# miditendo_rev2.net
KiCad netlist of a schematic drawn in EAGLE
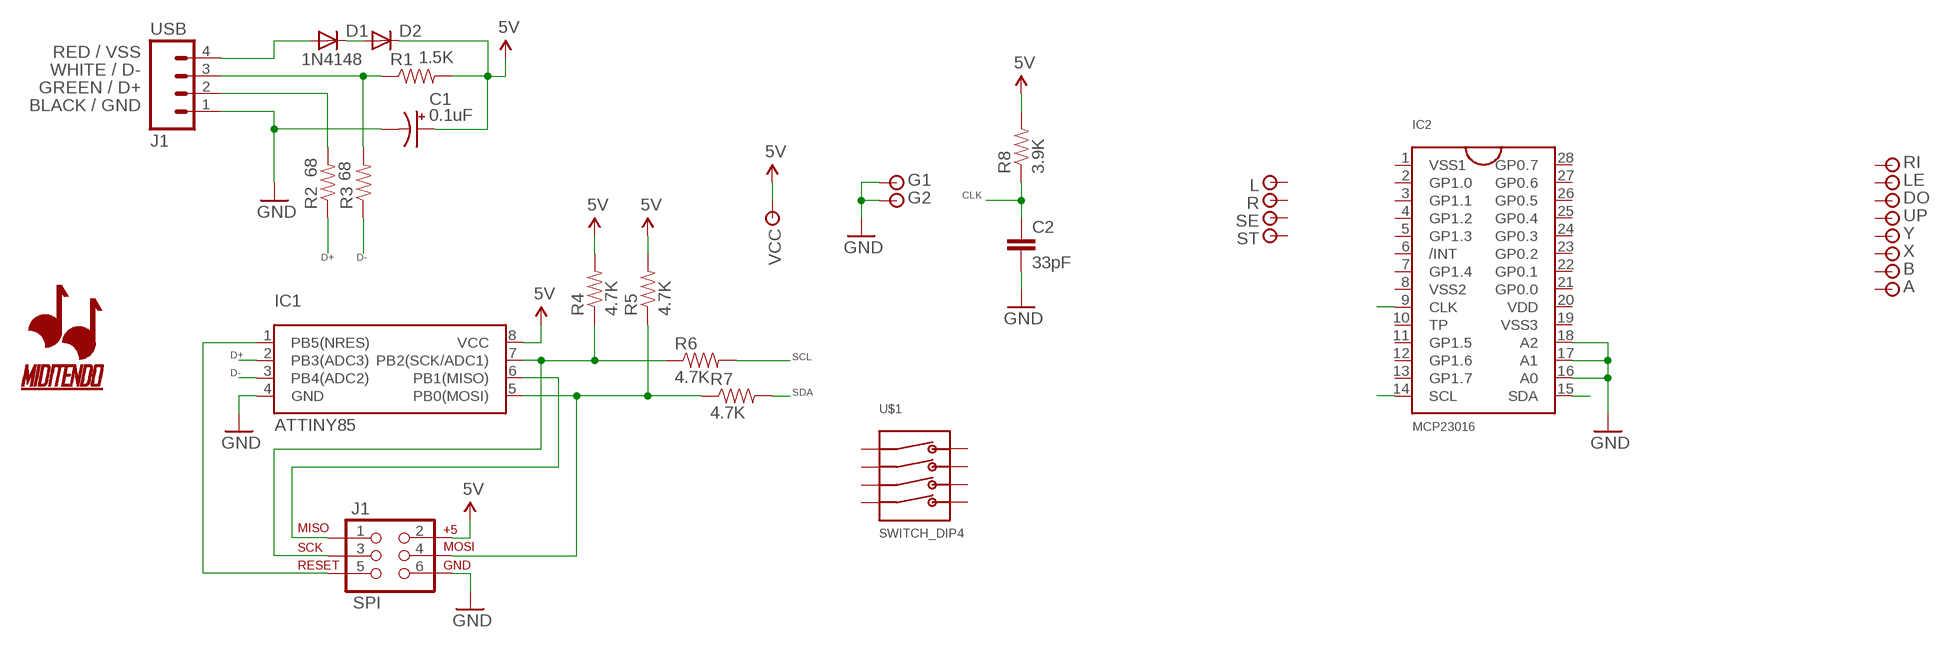
[diagram p0: schematic, sheet 1]

(export (version "E")
  (design (tool "Eeschema 10.0.6"))
  (components
    (comp (ref "A")
      (value "WIRE_JOINT")
      (footprint "eagle-import:THSOLDERPOINT")
      (libsource (lib "eagle-import") (part "WIRE_JOINT"))
    )
    (comp (ref "B")
      (value "WIRE_JOINT")
      (footprint "eagle-import:THSOLDERPOINT")
      (libsource (lib "eagle-import") (part "WIRE_JOINT"))
    )
    (comp (ref "C1")
      (value "0.1uF")
      (footprint "eagle-import:POLCAP_2.54")
      (libsource (lib "eagle-import") (part "POLARIZEDCAPACITORTH_2.54"))
    )
    (comp (ref "C2")
      (value "33pF")
      (footprint "eagle-import:0805")
      (libsource (lib "eagle-import") (part "CAPACITOR0805"))
    )
    (comp (ref "D1")
      (value "LL4148SOD-80C")
      (footprint "eagle-import:SOD-80C")
      (libsource (lib "eagle-import") (part "LL4148SOD-80C"))
    )
    (comp (ref "D2")
      (value "1N4148")
      (footprint "eagle-import:SOD-80C")
      (libsource (lib "eagle-import") (part "LL4148SOD-80C"))
    )
    (comp (ref "DO")
      (value "WIRE_JOINT")
      (footprint "eagle-import:THSOLDERPOINT")
      (libsource (lib "eagle-import") (part "WIRE_JOINT"))
    )
    (comp (ref "G1")
      (value "WIRE_JOINT")
      (footprint "eagle-import:THSOLDERPOINT")
      (libsource (lib "eagle-import") (part "WIRE_JOINT"))
    )
    (comp (ref "G2")
      (value "WIRE_JOINT")
      (footprint "eagle-import:THSOLDERPOINT")
      (libsource (lib "eagle-import") (part "WIRE_JOINT"))
    )
    (comp (ref "IC1")
      (value "ATTINY85")
      (footprint "eagle-import:SOIC8-EIAJ")
      (libsource (lib "eagle-import") (part "ATTINY85SOIC"))
    )
    (comp (ref "IC2")
      (value "MCP23016")
      (footprint "eagle-import:SOIC28")
      (libsource (lib "eagle-import") (part "MCP23016SOIC28"))
    )
    (comp (ref "J1")
      (value "SPI")
      (footprint "eagle-import:2X3-NS")
      (libsource (lib "eagle-import") (part "AVR_SPI_PRG_6NS"))
    )
    (comp (ref "L")
      (value "WIRE_JOINT")
      (footprint "eagle-import:THSOLDERPOINT")
      (libsource (lib "eagle-import") (part "WIRE_JOINT"))
    )
    (comp (ref "LE")
      (value "WIRE_JOINT")
      (footprint "eagle-import:THSOLDERPOINT")
      (libsource (lib "eagle-import") (part "WIRE_JOINT"))
    )
    (comp (ref "R")
      (value "WIRE_JOINT")
      (footprint "eagle-import:THSOLDERPOINT")
      (libsource (lib "eagle-import") (part "WIRE_JOINT"))
    )
    (comp (ref "R1")
      (value "1.5K")
      (footprint "eagle-import:0805")
      (libsource (lib "eagle-import") (part "RESISTOR0805"))
    )
    (comp (ref "R2")
      (value "68")
      (footprint "eagle-import:0805")
      (libsource (lib "eagle-import") (part "RESISTOR0805"))
    )
    (comp (ref "R3")
      (value "68")
      (footprint "eagle-import:0805")
      (libsource (lib "eagle-import") (part "RESISTOR0805"))
    )
    (comp (ref "R4")
      (value "4.7K")
      (footprint "eagle-import:0805")
      (libsource (lib "eagle-import") (part "RESISTOR0805"))
    )
    (comp (ref "R5")
      (value "4.7K")
      (footprint "eagle-import:0805")
      (libsource (lib "eagle-import") (part "RESISTOR0805"))
    )
    (comp (ref "R6")
      (value "4.7K")
      (footprint "eagle-import:0805")
      (libsource (lib "eagle-import") (part "RESISTOR0805"))
    )
    (comp (ref "R7")
      (value "4.7K")
      (footprint "eagle-import:0805")
      (libsource (lib "eagle-import") (part "RESISTOR0805"))
    )
    (comp (ref "R8")
      (value "3.9K")
      (footprint "eagle-import:0805")
      (libsource (lib "eagle-import") (part "RESISTOR0805"))
    )
    (comp (ref "RI")
      (value "WIRE_JOINT")
      (footprint "eagle-import:THSOLDERPOINT")
      (libsource (lib "eagle-import") (part "WIRE_JOINT"))
    )
    (comp (ref "SE")
      (value "WIRE_JOINT")
      (footprint "eagle-import:THSOLDERPOINT")
      (libsource (lib "eagle-import") (part "WIRE_JOINT"))
    )
    (comp (ref "ST")
      (value "WIRE_JOINT")
      (footprint "eagle-import:THSOLDERPOINT")
      (libsource (lib "eagle-import") (part "WIRE_JOINT"))
    )
    (comp (ref "U$1")
      (value "SWITCH_DIP4")
      (footprint "eagle-import:SWITCH_4DIP")
      (libsource (lib "eagle-import") (part "SWITCH_DIP4"))
    )
    (comp (ref "U$2")
      (value "MIDITENDO")
      (footprint "eagle-import:MIDITENDO")
      (libsource (lib "eagle-import") (part "MIDITENDO"))
    )
    (comp (ref "UP")
      (value "WIRE_JOINT")
      (footprint "eagle-import:THSOLDERPOINT")
      (libsource (lib "eagle-import") (part "WIRE_JOINT"))
    )
    (comp (ref "USB")
      (value "J1")
      (footprint "eagle-import:1X04_LONGPADS")
      (libsource (lib "eagle-import") (part "M04LONGPADS"))
    )
    (comp (ref "VCC")
      (value "WIRE_JOINT")
      (footprint "eagle-import:THSOLDERPOINT")
      (libsource (lib "eagle-import") (part "WIRE_JOINT"))
    )
    (comp (ref "X")
      (value "WIRE_JOINT")
      (footprint "eagle-import:THSOLDERPOINT")
      (libsource (lib "eagle-import") (part "WIRE_JOINT"))
    )
    (comp (ref "Y")
      (value "WIRE_JOINT")
      (footprint "eagle-import:THSOLDERPOINT")
      (libsource (lib "eagle-import") (part "WIRE_JOINT"))
    )
  )
  (nets
    (net (code "1") (name "/CLK") (class "Default")
      (node (ref "C2") (pin "1") (pinfunction "1_1") (pintype "passive"))
      (node (ref "IC2") (pin "9") (pinfunction "CLK_9") (pintype "input"))
      (node (ref "R8") (pin "1") (pinfunction "1_1") (pintype "passive"))
    )
    (net (code "2") (name "/D+") (class "Default")
      (node (ref "IC1") (pin "2") (pinfunction "PB3(ADC3)_2") (pintype "bidirectional"))
      (node (ref "R2") (pin "1") (pinfunction "1_1") (pintype "passive"))
    )
    (net (code "3") (name "/D-") (class "Default")
      (node (ref "IC1") (pin "3") (pinfunction "PB4(ADC2)_3") (pintype "bidirectional"))
      (node (ref "R3") (pin "1") (pinfunction "1_1") (pintype "passive"))
    )
    (net (code "4") (name "/SCL") (class "Default")
      (node (ref "IC2") (pin "14") (pinfunction "SCL_14") (pintype "input"))
      (node (ref "R6") (pin "2") (pinfunction "2_2") (pintype "passive"))
    )
    (net (code "5") (name "/SDA") (class "Default")
      (node (ref "IC2") (pin "15") (pinfunction "SDA_15") (pintype "bidirectional"))
      (node (ref "R7") (pin "2") (pinfunction "2_2") (pintype "passive"))
    )
    (net (code "6") (name "/VDD") (class "Default")
      (node (ref "IC2") (pin "20") (pinfunction "VDD_20") (pintype "power_in"))
    )
    (net (code "7") (name "/VSS1") (class "Default")
      (node (ref "IC2") (pin "1") (pinfunction "VSS1_1") (pintype "power_in"))
    )
    (net (code "8") (name "/VSS2") (class "Default")
      (node (ref "IC2") (pin "8") (pinfunction "VSS2_8") (pintype "power_in"))
    )
    (net (code "9") (name "/VSS3") (class "Default")
      (node (ref "IC2") (pin "19") (pinfunction "VSS3_19") (pintype "power_in"))
    )
    (net (code "10") (name "5V") (class "Default")
      (node (ref "C1") (pin "P") (pinfunction "+_P") (pintype "passive"))
      (node (ref "D2") (pin "PC") (pinfunction "C_PC") (pintype "passive"))
      (node (ref "IC1") (pin "8") (pinfunction "VCC_8") (pintype "bidirectional"))
      (node (ref "J1") (pin "2") (pinfunction "2_2") (pintype "passive"))
      (node (ref "R1") (pin "2") (pinfunction "2_2") (pintype "passive"))
      (node (ref "R4") (pin "2") (pinfunction "2_2") (pintype "passive"))
      (node (ref "R5") (pin "2") (pinfunction "2_2") (pintype "passive"))
      (node (ref "R8") (pin "2") (pinfunction "2_2") (pintype "passive"))
      (node (ref "VCC") (pin "P$1") (pinfunction "P$1_P$1") (pintype "passive"))
    )
    (net (code "11") (name "GND") (class "Default")
      (node (ref "C1") (pin "N") (pinfunction "-_N") (pintype "passive"))
      (node (ref "C2") (pin "2") (pinfunction "2_2") (pintype "passive"))
      (node (ref "G1") (pin "P$1") (pinfunction "P$1_P$1") (pintype "passive"))
      (node (ref "G2") (pin "P$1") (pinfunction "P$1_P$1") (pintype "passive"))
      (node (ref "IC1") (pin "4") (pinfunction "GND_4") (pintype "bidirectional"))
      (node (ref "IC2") (pin "16") (pinfunction "A0_16") (pintype "input"))
      (node (ref "IC2") (pin "17") (pinfunction "A1_17") (pintype "input"))
      (node (ref "IC2") (pin "18") (pinfunction "A2_18") (pintype "input"))
      (node (ref "J1") (pin "6") (pinfunction "6_6") (pintype "passive"))
      (node (ref "USB") (pin "1") (pinfunction "1_1") (pintype "passive"))
    )
    (net (code "12") (name "Net-(D1-A)") (class "Default")
      (node (ref "D1") (pin "PA") (pinfunction "A_PA") (pintype "passive"))
      (node (ref "USB") (pin "4") (pinfunction "4_4") (pintype "passive"))
    )
    (net (code "13") (name "Net-(D1-C)") (class "Default")
      (node (ref "D1") (pin "PC") (pinfunction "C_PC") (pintype "passive"))
      (node (ref "D2") (pin "PA") (pinfunction "A_PA") (pintype "passive"))
    )
    (net (code "14") (name "Net-(IC1-PB0(MOSI))") (class "Default")
      (node (ref "IC1") (pin "5") (pinfunction "PB0(MOSI)_5") (pintype "bidirectional"))
      (node (ref "J1") (pin "4") (pinfunction "4_4") (pintype "passive"))
      (node (ref "R5") (pin "1") (pinfunction "1_1") (pintype "passive"))
      (node (ref "R7") (pin "1") (pinfunction "1_1") (pintype "passive"))
    )
    (net (code "15") (name "Net-(IC1-PB1(MISO))") (class "Default")
      (node (ref "IC1") (pin "6") (pinfunction "PB1(MISO)_6") (pintype "bidirectional"))
      (node (ref "J1") (pin "1") (pinfunction "1_1") (pintype "passive"))
    )
    (net (code "16") (name "Net-(IC1-PB2(SCK{slash}ADC1))") (class "Default")
      (node (ref "IC1") (pin "7") (pinfunction "PB2(SCK/ADC1)_7") (pintype "bidirectional"))
      (node (ref "J1") (pin "3") (pinfunction "3_3") (pintype "passive"))
      (node (ref "R4") (pin "1") (pinfunction "1_1") (pintype "passive"))
      (node (ref "R6") (pin "1") (pinfunction "1_1") (pintype "passive"))
    )
    (net (code "17") (name "Net-(IC1-PB5(NRES))") (class "Default")
      (node (ref "IC1") (pin "1") (pinfunction "PB5(NRES)_1") (pintype "bidirectional"))
      (node (ref "J1") (pin "5") (pinfunction "5_5") (pintype "passive"))
    )
    (net (code "18") (name "Net-(R1-Pad1)") (class "Default")
      (node (ref "R1") (pin "1") (pinfunction "1_1") (pintype "passive"))
      (node (ref "R3") (pin "2") (pinfunction "2_2") (pintype "passive"))
      (node (ref "USB") (pin "3") (pinfunction "3_3") (pintype "passive"))
    )
    (net (code "19") (name "Net-(R2-Pad2)") (class "Default")
      (node (ref "R2") (pin "2") (pinfunction "2_2") (pintype "passive"))
      (node (ref "USB") (pin "2") (pinfunction "2_2") (pintype "passive"))
    )
    (net (code "20") (name "unconnected-(A-PadP$1)") (class "Default")
      (node (ref "A") (pin "P$1") (pinfunction "P$1_P$1") (pintype "passive"))
    )
    (net (code "21") (name "unconnected-(B-PadP$1)") (class "Default")
      (node (ref "B") (pin "P$1") (pinfunction "P$1_P$1") (pintype "passive"))
    )
    (net (code "22") (name "unconnected-(DO-PadP$1)") (class "Default")
      (node (ref "DO") (pin "P$1") (pinfunction "P$1_P$1") (pintype "passive"))
    )
    (net (code "23") (name "unconnected-(IC2-GP0.0-Pad21)") (class "Default")
      (node (ref "IC2") (pin "21") (pinfunction "GP0.0_21") (pintype "bidirectional"))
    )
    (net (code "24") (name "unconnected-(IC2-GP0.1-Pad22)") (class "Default")
      (node (ref "IC2") (pin "22") (pinfunction "GP0.1_22") (pintype "bidirectional"))
    )
    (net (code "25") (name "unconnected-(IC2-GP0.2-Pad23)") (class "Default")
      (node (ref "IC2") (pin "23") (pinfunction "GP0.2_23") (pintype "bidirectional"))
    )
    (net (code "26") (name "unconnected-(IC2-GP0.3-Pad24)") (class "Default")
      (node (ref "IC2") (pin "24") (pinfunction "GP0.3_24") (pintype "bidirectional"))
    )
    (net (code "27") (name "unconnected-(IC2-GP0.4-Pad25)") (class "Default")
      (node (ref "IC2") (pin "25") (pinfunction "GP0.4_25") (pintype "bidirectional"))
    )
    (net (code "28") (name "unconnected-(IC2-GP0.5-Pad26)") (class "Default")
      (node (ref "IC2") (pin "26") (pinfunction "GP0.5_26") (pintype "bidirectional"))
    )
    (net (code "29") (name "unconnected-(IC2-GP0.6-Pad27)") (class "Default")
      (node (ref "IC2") (pin "27") (pinfunction "GP0.6_27") (pintype "bidirectional"))
    )
    (net (code "30") (name "unconnected-(IC2-GP0.7-Pad28)") (class "Default")
      (node (ref "IC2") (pin "28") (pinfunction "GP0.7_28") (pintype "bidirectional"))
    )
    (net (code "31") (name "unconnected-(IC2-GP1.0-Pad2)") (class "Default")
      (node (ref "IC2") (pin "2") (pinfunction "GP1.0_2") (pintype "bidirectional"))
    )
    (net (code "32") (name "unconnected-(IC2-GP1.1-Pad3)") (class "Default")
      (node (ref "IC2") (pin "3") (pinfunction "GP1.1_3") (pintype "bidirectional"))
    )
    (net (code "33") (name "unconnected-(IC2-GP1.2-Pad4)") (class "Default")
      (node (ref "IC2") (pin "4") (pinfunction "GP1.2_4") (pintype "bidirectional"))
    )
    (net (code "34") (name "unconnected-(IC2-GP1.3-Pad5)") (class "Default")
      (node (ref "IC2") (pin "5") (pinfunction "GP1.3_5") (pintype "bidirectional"))
    )
    (net (code "35") (name "unconnected-(IC2-GP1.4-Pad7)") (class "Default")
      (node (ref "IC2") (pin "7") (pinfunction "GP1.4_7") (pintype "bidirectional"))
    )
    (net (code "36") (name "unconnected-(IC2-GP1.5-Pad11)") (class "Default")
      (node (ref "IC2") (pin "11") (pinfunction "GP1.5_11") (pintype "bidirectional"))
    )
    (net (code "37") (name "unconnected-(IC2-GP1.6-Pad12)") (class "Default")
      (node (ref "IC2") (pin "12") (pinfunction "GP1.6_12") (pintype "bidirectional"))
    )
    (net (code "38") (name "unconnected-(IC2-GP1.7-Pad13)") (class "Default")
      (node (ref "IC2") (pin "13") (pinfunction "GP1.7_13") (pintype "bidirectional"))
    )
    (net (code "39") (name "unconnected-(IC2-TP-Pad10)") (class "Default")
      (node (ref "IC2") (pin "10") (pinfunction "TP_10") (pintype "bidirectional"))
    )
    (net (code "40") (name "unconnected-(IC2-{slash}INT-Pad6)") (class "Default")
      (node (ref "IC2") (pin "6") (pinfunction "/INT_6") (pintype "output"))
    )
    (net (code "41") (name "unconnected-(L-PadP$1)") (class "Default")
      (node (ref "L") (pin "P$1") (pinfunction "P$1_P$1") (pintype "passive"))
    )
    (net (code "42") (name "unconnected-(LE-PadP$1)") (class "Default")
      (node (ref "LE") (pin "P$1") (pinfunction "P$1_P$1") (pintype "passive"))
    )
    (net (code "43") (name "unconnected-(R-PadP$1)") (class "Default")
      (node (ref "R") (pin "P$1") (pinfunction "P$1_P$1") (pintype "passive"))
    )
    (net (code "44") (name "unconnected-(RI-PadP$1)") (class "Default")
      (node (ref "RI") (pin "P$1") (pinfunction "P$1_P$1") (pintype "passive"))
    )
    (net (code "45") (name "unconnected-(SE-PadP$1)") (class "Default")
      (node (ref "SE") (pin "P$1") (pinfunction "P$1_P$1") (pintype "passive"))
    )
    (net (code "46") (name "unconnected-(ST-PadP$1)") (class "Default")
      (node (ref "ST") (pin "P$1") (pinfunction "P$1_P$1") (pintype "passive"))
    )
    (net (code "47") (name "unconnected-(U$1-PadP$1)") (class "Default")
      (node (ref "U$1") (pin "P$1") (pinfunction "P$1_P$1") (pintype "passive"))
    )
    (net (code "48") (name "unconnected-(U$1-PadP$2)") (class "Default")
      (node (ref "U$1") (pin "P$2") (pinfunction "P$2_P$2") (pintype "passive"))
    )
    (net (code "49") (name "unconnected-(U$1-PadP$3)") (class "Default")
      (node (ref "U$1") (pin "P$3") (pinfunction "P$3_P$3") (pintype "passive"))
    )
    (net (code "50") (name "unconnected-(U$1-PadP$4)") (class "Default")
      (node (ref "U$1") (pin "P$4") (pinfunction "P$4_P$4") (pintype "passive"))
    )
    (net (code "51") (name "unconnected-(U$1-PadP$5)") (class "Default")
      (node (ref "U$1") (pin "P$5") (pinfunction "P$5_P$5") (pintype "passive"))
    )
    (net (code "52") (name "unconnected-(U$1-PadP$6)") (class "Default")
      (node (ref "U$1") (pin "P$6") (pinfunction "P$6_P$6") (pintype "passive"))
    )
    (net (code "53") (name "unconnected-(U$1-PadP$7)") (class "Default")
      (node (ref "U$1") (pin "P$7") (pinfunction "P$7_P$7") (pintype "passive"))
    )
    (net (code "54") (name "unconnected-(U$1-PadP$8)") (class "Default")
      (node (ref "U$1") (pin "P$8") (pinfunction "P$8_P$8") (pintype "passive"))
    )
    (net (code "55") (name "unconnected-(UP-PadP$1)") (class "Default")
      (node (ref "UP") (pin "P$1") (pinfunction "P$1_P$1") (pintype "passive"))
    )
    (net (code "56") (name "unconnected-(X-PadP$1)") (class "Default")
      (node (ref "X") (pin "P$1") (pinfunction "P$1_P$1") (pintype "passive"))
    )
    (net (code "57") (name "unconnected-(Y-PadP$1)") (class "Default")
      (node (ref "Y") (pin "P$1") (pinfunction "P$1_P$1") (pintype "passive"))
    )
  )
)
